# 2_ADC.net
KiCad netlist of a schematic drawn in Altium Designer
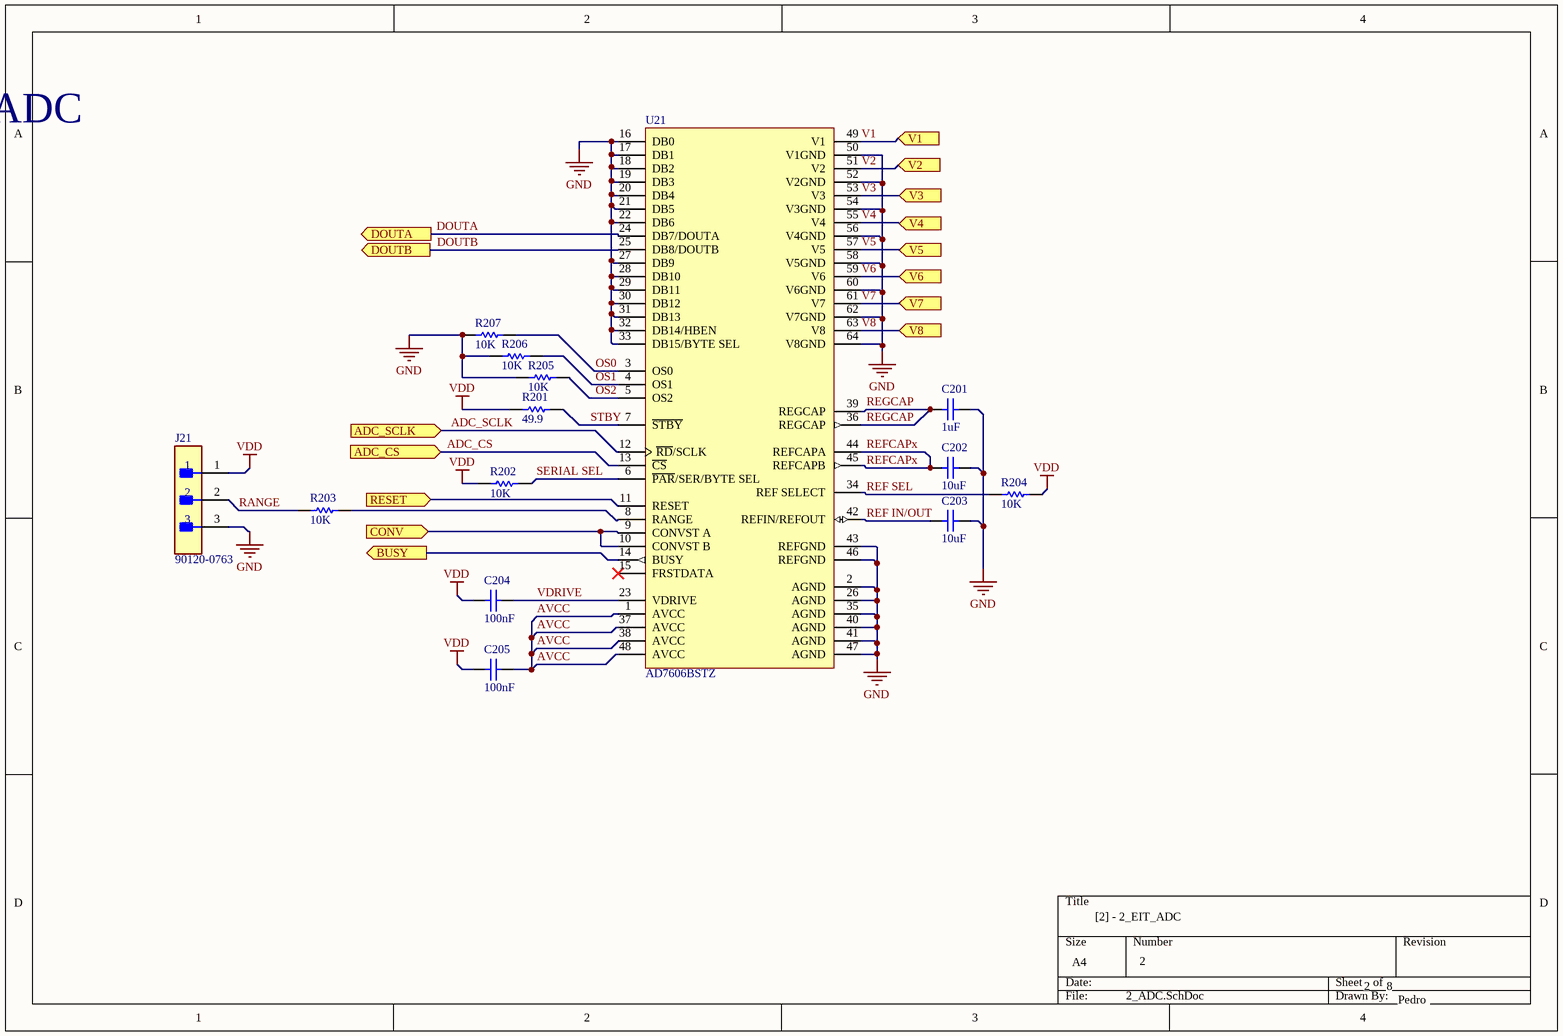
[diagram p0: 2_ADC.SchDoc]

(export (version "E")
  (design (tool "Eeschema 10.0.6"))
  (components
    (comp (ref "C201")
      (value "1uF")
      (footprint "CAPC1005X55X30LL05T10")
      (description "generic")
      (libsource (lib "RPI_EIT_SchLib") (part "Capacitor"))
    )
    (comp (ref "C202")
      (value "10uF")
      (footprint "CAPC1005X55X30LL05T10")
      (description "generic")
      (libsource (lib "RPI_EIT_SchLib") (part "Capacitor"))
    )
    (comp (ref "C203")
      (value "10uF")
      (footprint "CAPC1005X55X30LL05T10")
      (description "generic")
      (libsource (lib "RPI_EIT_SchLib") (part "Capacitor"))
    )
    (comp (ref "C204")
      (value "100nF")
      (footprint "CAPC1005X55X30LL05T10")
      (description "generic")
      (libsource (lib "RPI_EIT_SchLib") (part "Capacitor"))
    )
    (comp (ref "C205")
      (value "100nF")
      (footprint "CAPC1005X55X30LL05T10")
      (description "generic")
      (libsource (lib "RPI_EIT_SchLib") (part "Capacitor"))
    )
    (comp (ref "J21")
      (value "90120-0763")
      (footprint "FP-90120-0763-MFG")
      (description "CONN HEADER VERT 3POS 2.54MM")
      (fields
        (field (name "MANUFACTURER") "Molex")
        (field (name "OCTOPART") "https://octopart.com/90120-0763-molex-655433")
      )
      (libsource (lib "Altium Content Vault") (part "0d3f023dd272f625e17a2be33dea85f"))
    )
    (comp (ref "R201")
      (value "RC0603JR-070RL")
      (footprint "RESC1608X55X25LL10T15")
      (description "Chip Resistor, 0 Ohm, +/- 5%, 0.1 W, -55 to 155 degC, 0603 (1608 Metric), RoHS, Tape and Reel")
      (fields
        (field (name "TOLERANCE") "5%")
        (field (name "RESISTANCE") "49.9")
        (field (name "MANUFACTURER") "Yageo")
      )
      (libsource (lib "RPI_EIT_SchLib") (part "RES-2"))
    )
    (comp (ref "R202")
      (value "RC0603JR-070RL")
      (footprint "RESC1608X55X25LL10T15")
      (description "Chip Resistor, 0 Ohm, +/- 5%, 0.1 W, -55 to 155 degC, 0603 (1608 Metric), RoHS, Tape and Reel")
      (fields
        (field (name "TOLERANCE") "5%")
        (field (name "RESISTANCE") "10K")
        (field (name "MANUFACTURER") "Yageo")
      )
      (libsource (lib "RPI_EIT_SchLib") (part "RES-2"))
    )
    (comp (ref "R203")
      (value "RC0603JR-070RL")
      (footprint "RESC1608X55X25LL10T15")
      (description "Chip Resistor, 0 Ohm, +/- 5%, 0.1 W, -55 to 155 degC, 0603 (1608 Metric), RoHS, Tape and Reel")
      (fields
        (field (name "TOLERANCE") "5%")
        (field (name "RESISTANCE") "10K")
        (field (name "MANUFACTURER") "Yageo")
      )
      (libsource (lib "RPI_EIT_SchLib") (part "RES-2"))
    )
    (comp (ref "R204")
      (value "RC0603JR-070RL")
      (footprint "RESC1608X55X25LL10T15")
      (description "Chip Resistor, 0 Ohm, +/- 5%, 0.1 W, -55 to 155 degC, 0603 (1608 Metric), RoHS, Tape and Reel")
      (fields
        (field (name "TOLERANCE") "5%")
        (field (name "RESISTANCE") "10K")
        (field (name "MANUFACTURER") "Yageo")
      )
      (libsource (lib "RPI_EIT_SchLib") (part "RES-2"))
    )
    (comp (ref "R205")
      (value "RC0603JR-070RL")
      (footprint "RESC1608X55X25LL10T15")
      (description "Chip Resistor, 0 Ohm, +/- 5%, 0.1 W, -55 to 155 degC, 0603 (1608 Metric), RoHS, Tape and Reel")
      (fields
        (field (name "TOLERANCE") "5%")
        (field (name "RESISTANCE") "10K")
        (field (name "MANUFACTURER") "Yageo")
      )
      (libsource (lib "RPI_EIT_SchLib") (part "RES-2"))
    )
    (comp (ref "R206")
      (value "RC0603JR-070RL")
      (footprint "RESC1608X55X25LL10T15")
      (description "Chip Resistor, 0 Ohm, +/- 5%, 0.1 W, -55 to 155 degC, 0603 (1608 Metric), RoHS, Tape and Reel")
      (fields
        (field (name "TOLERANCE") "5%")
        (field (name "RESISTANCE") "10K")
        (field (name "MANUFACTURER") "Yageo")
      )
      (libsource (lib "RPI_EIT_SchLib") (part "RES-2"))
    )
    (comp (ref "R207")
      (value "RC0603JR-070RL")
      (footprint "RESC1608X55X25LL10T15")
      (description "Chip Resistor, 0 Ohm, +/- 5%, 0.1 W, -55 to 155 degC, 0603 (1608 Metric), RoHS, Tape and Reel")
      (fields
        (field (name "TOLERANCE") "5%")
        (field (name "RESISTANCE") "10K")
        (field (name "MANUFACTURER") "Yageo")
      )
      (libsource (lib "RPI_EIT_SchLib") (part "RES-2"))
    )
    (comp (ref "U21")
      (value "AD7606BSTZ")
      (footprint "ST-64-2_L")
      (fields (field (name "GENERIC PART NUMBER") "AD7606") (field (name "MANUFACTURER") "Analog Devices"))
      (libsource (lib "Altium Content Vault") (part "ADI-AD7606-ST-64-2"))
    )
  )
  (nets
    (net (code "1") (name "/ADC_CS") (class "Default")
      (node (ref "U21") (pin "13") (pinfunction "~{CS}_13") (pintype "passive"))
    )
    (net (code "2") (name "/ADC_SCLK") (class "Default")
      (node (ref "U21") (pin "12") (pinfunction "~{RD}/SCLK_12") (pintype "passive"))
    )
    (net (code "3") (name "/AVCC") (class "Default")
      (node (ref "C205") (pin "1") (pinfunction "1_1") (pintype "passive"))
      (node (ref "U21") (pin "1") (pinfunction "AVCC_1") (pintype "power_in"))
      (node (ref "U21") (pin "37") (pinfunction "AVCC_37") (pintype "power_in"))
      (node (ref "U21") (pin "38") (pinfunction "AVCC_38") (pintype "power_in"))
      (node (ref "U21") (pin "48") (pinfunction "AVCC_48") (pintype "power_in"))
    )
    (net (code "4") (name "/BUSY") (class "Default")
      (node (ref "U21") (pin "14") (pinfunction "BUSY_14") (pintype "output"))
    )
    (net (code "5") (name "/CONV") (class "Default")
      (node (ref "U21") (pin "10") (pinfunction "CONVST_B_10") (pintype "passive"))
      (node (ref "U21") (pin "9") (pinfunction "CONVST_A_9") (pintype "passive"))
    )
    (net (code "6") (name "/DOUTA") (class "Default")
      (node (ref "U21") (pin "24") (pinfunction "DB7/DOUTA_24") (pintype "passive"))
    )
    (net (code "7") (name "/DOUTB") (class "Default")
      (node (ref "U21") (pin "25") (pinfunction "DB8/DOUTB_25") (pintype "passive"))
    )
    (net (code "8") (name "/OS0") (class "Default")
      (node (ref "R207") (pin "1") (pinfunction "1_1") (pintype "passive"))
      (node (ref "U21") (pin "3") (pinfunction "OS0_3") (pintype "passive"))
    )
    (net (code "9") (name "/OS1") (class "Default")
      (node (ref "R206") (pin "1") (pinfunction "1_1") (pintype "passive"))
      (node (ref "U21") (pin "4") (pinfunction "OS1_4") (pintype "passive"))
    )
    (net (code "10") (name "/OS2") (class "Default")
      (node (ref "R205") (pin "1") (pinfunction "1_1") (pintype "passive"))
      (node (ref "U21") (pin "5") (pinfunction "OS2_5") (pintype "passive"))
    )
    (net (code "11") (name "/RANGE") (class "Default")
      (node (ref "J21") (pin "2") (pinfunction "2_2") (pintype "passive"))
      (node (ref "R203") (pin "2") (pinfunction "2_2") (pintype "passive"))
    )
    (net (code "12") (name "/REF IN{slash}OUT") (class "Default")
      (node (ref "C203") (pin "2") (pinfunction "2_2") (pintype "passive"))
      (node (ref "U21") (pin "42") (pinfunction "REFIN/REFOUT_42") (pintype "bidirectional"))
    )
    (net (code "13") (name "/REF SEL") (class "Default")
      (node (ref "R204") (pin "2") (pinfunction "2_2") (pintype "passive"))
      (node (ref "U21") (pin "34") (pinfunction "REF_SELECT_34") (pintype "passive"))
    )
    (net (code "14") (name "/REFCAPx") (class "Default")
      (node (ref "C202") (pin "2") (pinfunction "2_2") (pintype "passive"))
      (node (ref "U21") (pin "44") (pinfunction "REFCAPA_44") (pintype "passive"))
      (node (ref "U21") (pin "45") (pinfunction "REFCAPB_45") (pintype "output"))
    )
    (net (code "15") (name "/REGCAP") (class "Default")
      (node (ref "C201") (pin "2") (pinfunction "2_2") (pintype "passive"))
      (node (ref "U21") (pin "36") (pinfunction "REGCAP_36") (pintype "output"))
      (node (ref "U21") (pin "39") (pinfunction "REGCAP_39") (pintype "passive"))
    )
    (net (code "16") (name "/RESET") (class "Default")
      (node (ref "U21") (pin "11") (pinfunction "RESET_11") (pintype "passive"))
    )
    (net (code "17") (name "/SERIAL SEL") (class "Default")
      (node (ref "R202") (pin "1") (pinfunction "1_1") (pintype "passive"))
      (node (ref "U21") (pin "6") (pinfunction "~{PAR}/SER/BYTE_SEL_6") (pintype "passive"))
    )
    (net (code "18") (name "/STBY") (class "Default")
      (node (ref "R201") (pin "1") (pinfunction "1_1") (pintype "passive"))
      (node (ref "U21") (pin "7") (pinfunction "~{STBY}_7") (pintype "passive"))
    )
    (net (code "19") (name "/V1") (class "Default")
      (node (ref "U21") (pin "49") (pinfunction "V1_49") (pintype "passive"))
    )
    (net (code "20") (name "/V2") (class "Default")
      (node (ref "U21") (pin "51") (pinfunction "V2_51") (pintype "passive"))
    )
    (net (code "21") (name "/V3") (class "Default")
      (node (ref "U21") (pin "53") (pinfunction "V3_53") (pintype "passive"))
    )
    (net (code "22") (name "/V4") (class "Default")
      (node (ref "U21") (pin "55") (pinfunction "V4_55") (pintype "passive"))
    )
    (net (code "23") (name "/V5") (class "Default")
      (node (ref "U21") (pin "57") (pinfunction "V5_57") (pintype "passive"))
    )
    (net (code "24") (name "/V6") (class "Default")
      (node (ref "U21") (pin "59") (pinfunction "V6_59") (pintype "passive"))
    )
    (net (code "25") (name "/V7") (class "Default")
      (node (ref "U21") (pin "61") (pinfunction "V7_61") (pintype "passive"))
    )
    (net (code "26") (name "/V8") (class "Default")
      (node (ref "U21") (pin "63") (pinfunction "V8_63") (pintype "passive"))
    )
    (net (code "27") (name "/VDRIVE") (class "Default")
      (node (ref "C204") (pin "1") (pinfunction "1_1") (pintype "passive"))
      (node (ref "U21") (pin "23") (pinfunction "VDRIVE_23") (pintype "power_in"))
    )
    (net (code "28") (name "GND") (class "Default")
      (node (ref "C201") (pin "1") (pinfunction "1_1") (pintype "passive"))
      (node (ref "C202") (pin "1") (pinfunction "1_1") (pintype "passive"))
      (node (ref "C203") (pin "1") (pinfunction "1_1") (pintype "passive"))
      (node (ref "J21") (pin "3") (pinfunction "3_3") (pintype "passive"))
      (node (ref "R205") (pin "2") (pinfunction "2_2") (pintype "passive"))
      (node (ref "R206") (pin "2") (pinfunction "2_2") (pintype "passive"))
      (node (ref "R207") (pin "2") (pinfunction "2_2") (pintype "passive"))
      (node (ref "U21") (pin "16") (pinfunction "DB0_16") (pintype "passive"))
      (node (ref "U21") (pin "17") (pinfunction "DB1_17") (pintype "passive"))
      (node (ref "U21") (pin "18") (pinfunction "DB2_18") (pintype "passive"))
      (node (ref "U21") (pin "19") (pinfunction "DB3_19") (pintype "passive"))
      (node (ref "U21") (pin "2") (pinfunction "AGND_2") (pintype "power_in"))
      (node (ref "U21") (pin "20") (pinfunction "DB4_20") (pintype "passive"))
      (node (ref "U21") (pin "21") (pinfunction "DB5_21") (pintype "passive"))
      (node (ref "U21") (pin "22") (pinfunction "DB6_22") (pintype "passive"))
      (node (ref "U21") (pin "26") (pinfunction "AGND_26") (pintype "power_in"))
      (node (ref "U21") (pin "27") (pinfunction "DB9_27") (pintype "passive"))
      (node (ref "U21") (pin "28") (pinfunction "DB10_28") (pintype "passive"))
      (node (ref "U21") (pin "29") (pinfunction "DB11_29") (pintype "passive"))
      (node (ref "U21") (pin "30") (pinfunction "DB12_30") (pintype "passive"))
      (node (ref "U21") (pin "31") (pinfunction "DB13_31") (pintype "passive"))
      (node (ref "U21") (pin "32") (pinfunction "DB14/HBEN_32") (pintype "passive"))
      (node (ref "U21") (pin "33") (pinfunction "DB15/BYTE_SEL_33") (pintype "passive"))
      (node (ref "U21") (pin "35") (pinfunction "AGND_35") (pintype "power_in"))
      (node (ref "U21") (pin "40") (pinfunction "AGND_40") (pintype "power_in"))
      (node (ref "U21") (pin "41") (pinfunction "AGND_41") (pintype "power_in"))
      (node (ref "U21") (pin "43") (pinfunction "REFGND_43") (pintype "power_in"))
      (node (ref "U21") (pin "46") (pinfunction "REFGND_46") (pintype "power_in"))
      (node (ref "U21") (pin "47") (pinfunction "AGND_47") (pintype "power_in"))
      (node (ref "U21") (pin "50") (pinfunction "V1GND_50") (pintype "power_in"))
      (node (ref "U21") (pin "52") (pinfunction "V2GND_52") (pintype "power_in"))
      (node (ref "U21") (pin "54") (pinfunction "V3GND_54") (pintype "power_in"))
      (node (ref "U21") (pin "56") (pinfunction "V4GND_56") (pintype "power_in"))
      (node (ref "U21") (pin "58") (pinfunction "V5GND_58") (pintype "power_in"))
      (node (ref "U21") (pin "60") (pinfunction "V6GND_60") (pintype "power_in"))
      (node (ref "U21") (pin "62") (pinfunction "V7GND_62") (pintype "power_in"))
      (node (ref "U21") (pin "64") (pinfunction "V8GND_64") (pintype "power_in"))
    )
    (net (code "29") (name "Net-(U21-RANGE)") (class "Default")
      (node (ref "R203") (pin "1") (pinfunction "1_1") (pintype "passive"))
      (node (ref "U21") (pin "8") (pinfunction "RANGE_8") (pintype "passive"))
    )
    (net (code "30") (name "VDD") (class "Default")
      (node (ref "C204") (pin "2") (pinfunction "2_2") (pintype "passive"))
      (node (ref "C205") (pin "2") (pinfunction "2_2") (pintype "passive"))
      (node (ref "J21") (pin "1") (pinfunction "1_1") (pintype "passive"))
      (node (ref "R201") (pin "2") (pinfunction "2_2") (pintype "passive"))
      (node (ref "R202") (pin "2") (pinfunction "2_2") (pintype "passive"))
      (node (ref "R204") (pin "1") (pinfunction "1_1") (pintype "passive"))
    )
    (net (code "31") (name "unconnected-(U21-FRSTDATA-Pad15)") (class "Default")
      (node (ref "U21") (pin "15") (pinfunction "FRSTDATA_15") (pintype "tri_state+no_connect"))
    )
  )
)
